# P4_LEDS.net
KiCad netlist of a schematic drawn in Altium Designer
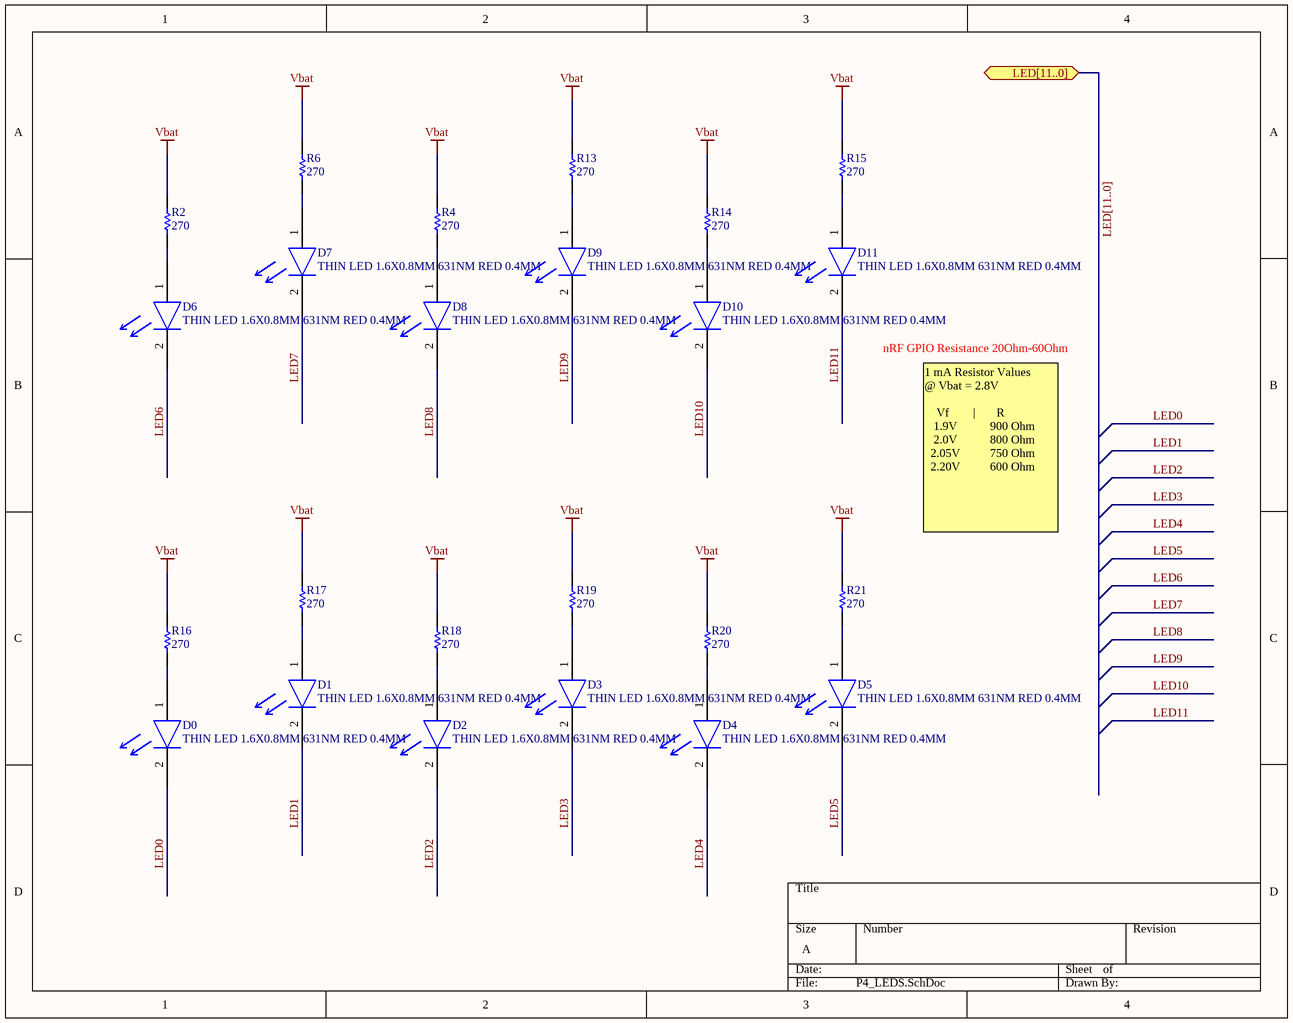
[diagram p0: P4_LEDS.SchDoc]

(export (version "E")
  (design (tool "Eeschema 10.0.6"))
  (components
    (comp (ref "D0")
      (value "THIN LED 1.6X0.8MM 631NM RED 0.4MM")
      (footprint "LEDC0603(1608)_N")
      (description "Light Emitting Diode")
      (libsource (lib "Arena_Lib") (part "LED"))
    )
    (comp (ref "D1")
      (value "THIN LED 1.6X0.8MM 631NM RED 0.4MM")
      (footprint "LEDC0603(1608)_N")
      (description "Light Emitting Diode")
      (libsource (lib "Arena_Lib") (part "LED"))
    )
    (comp (ref "D2")
      (value "THIN LED 1.6X0.8MM 631NM RED 0.4MM")
      (footprint "LEDC0603(1608)_N")
      (description "Light Emitting Diode")
      (libsource (lib "Arena_Lib") (part "LED"))
    )
    (comp (ref "D3")
      (value "THIN LED 1.6X0.8MM 631NM RED 0.4MM")
      (footprint "LEDC0603(1608)_N")
      (description "Light Emitting Diode")
      (libsource (lib "Arena_Lib") (part "LED"))
    )
    (comp (ref "D4")
      (value "THIN LED 1.6X0.8MM 631NM RED 0.4MM")
      (footprint "LEDC0603(1608)_N")
      (description "Light Emitting Diode")
      (libsource (lib "Arena_Lib") (part "LED"))
    )
    (comp (ref "D5")
      (value "THIN LED 1.6X0.8MM 631NM RED 0.4MM")
      (footprint "LEDC0603(1608)_N")
      (description "Light Emitting Diode")
      (libsource (lib "Arena_Lib") (part "LED"))
    )
    (comp (ref "D6")
      (value "THIN LED 1.6X0.8MM 631NM RED 0.4MM")
      (footprint "LEDC0603(1608)_N")
      (description "Light Emitting Diode")
      (libsource (lib "Arena_Lib") (part "LED"))
    )
    (comp (ref "D7")
      (value "THIN LED 1.6X0.8MM 631NM RED 0.4MM")
      (footprint "LEDC0603(1608)_N")
      (description "Light Emitting Diode")
      (libsource (lib "Arena_Lib") (part "LED"))
    )
    (comp (ref "D8")
      (value "THIN LED 1.6X0.8MM 631NM RED 0.4MM")
      (footprint "LEDC0603(1608)_N")
      (description "Light Emitting Diode")
      (libsource (lib "Arena_Lib") (part "LED"))
    )
    (comp (ref "D9")
      (value "THIN LED 1.6X0.8MM 631NM RED 0.4MM")
      (footprint "LEDC0603(1608)_N")
      (description "Light Emitting Diode")
      (libsource (lib "Arena_Lib") (part "LED"))
    )
    (comp (ref "D10")
      (value "THIN LED 1.6X0.8MM 631NM RED 0.4MM")
      (footprint "LEDC0603(1608)_N")
      (description "Light Emitting Diode")
      (libsource (lib "Arena_Lib") (part "LED"))
    )
    (comp (ref "D11")
      (value "THIN LED 1.6X0.8MM 631NM RED 0.4MM")
      (footprint "LEDC0603(1608)_N")
      (description "Light Emitting Diode")
      (libsource (lib "Arena_Lib") (part "LED"))
    )
    (comp (ref "R2")
      (value "270")
      (footprint "RESC0201(0603)_N")
      (fields (field (name "TOLERANCE") "+/-5%") (field (name "Comment") "RES 270 OHM 1/20W 5% 0201 SMD"))
      (libsource (lib "Arena_Lib") (part "RES"))
    )
    (comp (ref "R4")
      (value "270")
      (footprint "RESC0201(0603)_N")
      (fields (field (name "TOLERANCE") "+/-5%") (field (name "Comment") "RES 270 OHM 1/20W 5% 0201 SMD"))
      (libsource (lib "Arena_Lib") (part "RES"))
    )
    (comp (ref "R6")
      (value "270")
      (footprint "RESC0201(0603)_N")
      (fields (field (name "TOLERANCE") "+/-5%") (field (name "Comment") "RES 270 OHM 1/20W 5% 0201 SMD"))
      (libsource (lib "Arena_Lib") (part "RES"))
    )
    (comp (ref "R13")
      (value "270")
      (footprint "RESC0201(0603)_N")
      (fields (field (name "TOLERANCE") "+/-5%") (field (name "Comment") "RES 270 OHM 1/20W 5% 0201 SMD"))
      (libsource (lib "Arena_Lib") (part "RES"))
    )
    (comp (ref "R14")
      (value "270")
      (footprint "RESC0201(0603)_N")
      (fields (field (name "TOLERANCE") "+/-5%") (field (name "Comment") "RES 270 OHM 1/20W 5% 0201 SMD"))
      (libsource (lib "Arena_Lib") (part "RES"))
    )
    (comp (ref "R15")
      (value "270")
      (footprint "RESC0201(0603)_N")
      (fields (field (name "TOLERANCE") "+/-5%") (field (name "Comment") "RES 270 OHM 1/20W 5% 0201 SMD"))
      (libsource (lib "Arena_Lib") (part "RES"))
    )
    (comp (ref "R16")
      (value "270")
      (footprint "RESC0201(0603)_N")
      (fields (field (name "TOLERANCE") "+/-5%") (field (name "Comment") "RES 270 OHM 1/20W 5% 0201 SMD"))
      (libsource (lib "Arena_Lib") (part "RES"))
    )
    (comp (ref "R17")
      (value "270")
      (footprint "RESC0201(0603)_N")
      (fields (field (name "TOLERANCE") "+/-5%") (field (name "Comment") "RES 270 OHM 1/20W 5% 0201 SMD"))
      (libsource (lib "Arena_Lib") (part "RES"))
    )
    (comp (ref "R18")
      (value "270")
      (footprint "RESC0201(0603)_N")
      (fields (field (name "TOLERANCE") "+/-5%") (field (name "Comment") "RES 270 OHM 1/20W 5% 0201 SMD"))
      (libsource (lib "Arena_Lib") (part "RES"))
    )
    (comp (ref "R19")
      (value "270")
      (footprint "RESC0201(0603)_N")
      (fields (field (name "TOLERANCE") "+/-5%") (field (name "Comment") "RES 270 OHM 1/20W 5% 0201 SMD"))
      (libsource (lib "Arena_Lib") (part "RES"))
    )
    (comp (ref "R20")
      (value "270")
      (footprint "RESC0201(0603)_N")
      (fields (field (name "TOLERANCE") "+/-5%") (field (name "Comment") "RES 270 OHM 1/20W 5% 0201 SMD"))
      (libsource (lib "Arena_Lib") (part "RES"))
    )
    (comp (ref "R21")
      (value "270")
      (footprint "RESC0201(0603)_N")
      (fields (field (name "TOLERANCE") "+/-5%") (field (name "Comment") "RES 270 OHM 1/20W 5% 0201 SMD"))
      (libsource (lib "Arena_Lib") (part "RES"))
    )
  )
  (nets
    (net (code "1") (name "/LED0") (class "Default")
      (node (ref "D0") (pin "2") (pinfunction "Cathode_2") (pintype "passive"))
    )
    (net (code "2") (name "/LED1") (class "Default")
      (node (ref "D1") (pin "2") (pinfunction "Cathode_2") (pintype "passive"))
    )
    (net (code "3") (name "/LED2") (class "Default")
      (node (ref "D2") (pin "2") (pinfunction "Cathode_2") (pintype "passive"))
    )
    (net (code "4") (name "/LED3") (class "Default")
      (node (ref "D3") (pin "2") (pinfunction "Cathode_2") (pintype "passive"))
    )
    (net (code "5") (name "/LED4") (class "Default")
      (node (ref "D4") (pin "2") (pinfunction "Cathode_2") (pintype "passive"))
    )
    (net (code "6") (name "/LED5") (class "Default")
      (node (ref "D5") (pin "2") (pinfunction "Cathode_2") (pintype "passive"))
    )
    (net (code "7") (name "/LED6") (class "Default")
      (node (ref "D6") (pin "2") (pinfunction "Cathode_2") (pintype "passive"))
    )
    (net (code "8") (name "/LED7") (class "Default")
      (node (ref "D7") (pin "2") (pinfunction "Cathode_2") (pintype "passive"))
    )
    (net (code "9") (name "/LED8") (class "Default")
      (node (ref "D8") (pin "2") (pinfunction "Cathode_2") (pintype "passive"))
    )
    (net (code "10") (name "/LED9") (class "Default")
      (node (ref "D9") (pin "2") (pinfunction "Cathode_2") (pintype "passive"))
    )
    (net (code "11") (name "/LED10") (class "Default")
      (node (ref "D10") (pin "2") (pinfunction "Cathode_2") (pintype "passive"))
    )
    (net (code "12") (name "/LED11") (class "Default")
      (node (ref "D11") (pin "2") (pinfunction "Cathode_2") (pintype "passive"))
    )
    (net (code "14") (name "Net-(D0-anode)") (class "Default")
      (node (ref "D0") (pin "1") (pinfunction "anode_1") (pintype "passive"))
      (node (ref "R16") (pin "2") (pintype "power_in"))
    )
    (net (code "15") (name "Net-(D1-anode)") (class "Default")
      (node (ref "D1") (pin "1") (pinfunction "anode_1") (pintype "passive"))
      (node (ref "R17") (pin "2") (pintype "power_in"))
    )
    (net (code "16") (name "Net-(D2-anode)") (class "Default")
      (node (ref "D2") (pin "1") (pinfunction "anode_1") (pintype "passive"))
      (node (ref "R18") (pin "2") (pintype "power_in"))
    )
    (net (code "17") (name "Net-(D3-anode)") (class "Default")
      (node (ref "D3") (pin "1") (pinfunction "anode_1") (pintype "passive"))
      (node (ref "R19") (pin "2") (pintype "power_in"))
    )
    (net (code "18") (name "Net-(D4-anode)") (class "Default")
      (node (ref "D4") (pin "1") (pinfunction "anode_1") (pintype "passive"))
      (node (ref "R20") (pin "2") (pintype "power_in"))
    )
    (net (code "19") (name "Net-(D5-anode)") (class "Default")
      (node (ref "D5") (pin "1") (pinfunction "anode_1") (pintype "passive"))
      (node (ref "R21") (pin "2") (pintype "power_in"))
    )
    (net (code "20") (name "Net-(D6-anode)") (class "Default")
      (node (ref "D6") (pin "1") (pinfunction "anode_1") (pintype "passive"))
      (node (ref "R2") (pin "2") (pintype "power_in"))
    )
    (net (code "21") (name "Net-(D7-anode)") (class "Default")
      (node (ref "D7") (pin "1") (pinfunction "anode_1") (pintype "passive"))
      (node (ref "R6") (pin "2") (pintype "power_in"))
    )
    (net (code "22") (name "Net-(D8-anode)") (class "Default")
      (node (ref "D8") (pin "1") (pinfunction "anode_1") (pintype "passive"))
      (node (ref "R4") (pin "2") (pintype "power_in"))
    )
    (net (code "23") (name "Net-(D9-anode)") (class "Default")
      (node (ref "D9") (pin "1") (pinfunction "anode_1") (pintype "passive"))
      (node (ref "R13") (pin "2") (pintype "power_in"))
    )
    (net (code "24") (name "Net-(D10-anode)") (class "Default")
      (node (ref "D10") (pin "1") (pinfunction "anode_1") (pintype "passive"))
      (node (ref "R14") (pin "2") (pintype "power_in"))
    )
    (net (code "25") (name "Net-(D11-anode)") (class "Default")
      (node (ref "D11") (pin "1") (pinfunction "anode_1") (pintype "passive"))
      (node (ref "R15") (pin "2") (pintype "power_in"))
    )
    (net (code "26") (name "Vbat") (class "Default")
      (node (ref "R13") (pin "1") (pintype "power_in"))
      (node (ref "R14") (pin "1") (pintype "power_in"))
      (node (ref "R15") (pin "1") (pintype "power_in"))
      (node (ref "R16") (pin "1") (pintype "power_in"))
      (node (ref "R17") (pin "1") (pintype "power_in"))
      (node (ref "R18") (pin "1") (pintype "power_in"))
      (node (ref "R19") (pin "1") (pintype "power_in"))
      (node (ref "R2") (pin "1") (pintype "power_in"))
      (node (ref "R20") (pin "1") (pintype "power_in"))
      (node (ref "R21") (pin "1") (pintype "power_in"))
      (node (ref "R4") (pin "1") (pintype "power_in"))
      (node (ref "R6") (pin "1") (pintype "power_in"))
    )
  )
)
